# Digital_Isolation.net
KiCad netlist of a schematic drawn in Altium Designer
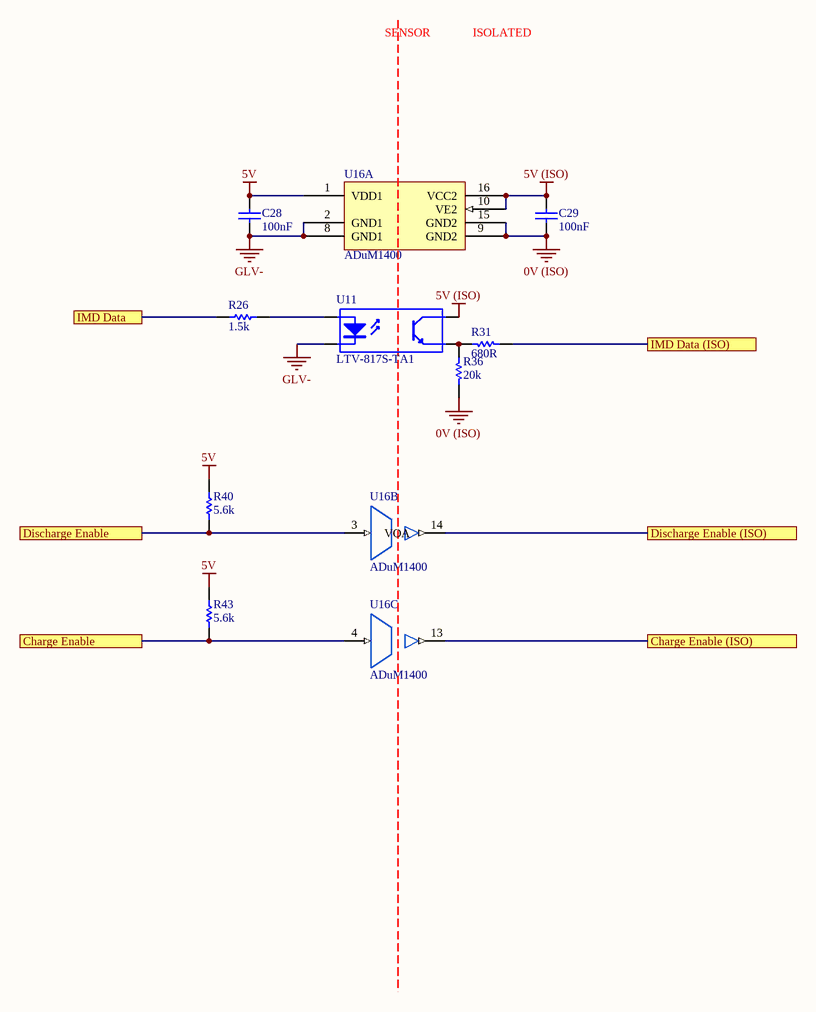
[diagram p0: Digital Isolation.SchDoc]

(export (version "E")
  (design (tool "Eeschema 10.0.6"))
  (components
    (comp (ref "C28")
      (value "100nF")
      (footprint "0805")
      (fields
        (field (name "PART NUMBER") "GCM21BR71E104KA37L")
        (field (name "TOLERANCE") "10%")
        (field (name "MANUFACTURER") "muRata")
      )
      (libsource (lib "ts_20-standard-library") (part "Capacitor"))
    )
    (comp (ref "C29")
      (value "100nF")
      (footprint "0805")
      (fields
        (field (name "PART NUMBER") "GCM21BR71E104KA37L")
        (field (name "TOLERANCE") "10%")
        (field (name "MANUFACTURER") "muRata")
      )
      (libsource (lib "ts_20-standard-library") (part "Capacitor"))
    )
    (comp (ref "R26")
      (value "1.5k")
      (footprint "0805")
      (fields
        (field (name "PART NUMBER") "RC0805FR071K5L")
        (field (name "MANUFACTURER") "YAGEO")
        (field (name "TOLERANCE") "0.01")
      )
      (libsource (lib "ts_20-standard-library") (part "Resistor"))
    )
    (comp (ref "R31")
      (value "680R")
      (footprint "0805")
      (fields
        (field (name "PART NUMBER") "RC0805FR07680RL")
        (field (name "MANUFACTURER") "YAGEO")
        (field (name "TOLERANCE") "0.01")
      )
      (libsource (lib "ts_20-standard-library") (part "Resistor"))
    )
    (comp (ref "R36")
      (value "20k")
      (footprint "0805")
      (fields
        (field (name "PART NUMBER") "RC0805FR0720KL")
        (field (name "MANUFACTURER") "YAGEO")
        (field (name "TOLERANCE") "0.01")
      )
      (libsource (lib "ts_20-standard-library") (part "Resistor"))
    )
    (comp (ref "R40")
      (value "5.6k")
      (footprint "0805")
      (fields
        (field (name "PART NUMBER") "RC0805FR075K6L")
        (field (name "MANUFACTURER") "YAGEO")
        (field (name "TOLERANCE") "0.01")
      )
      (libsource (lib "ts_20-standard-library") (part "Resistor"))
    )
    (comp (ref "R43")
      (value "5.6k")
      (footprint "0805")
      (fields
        (field (name "PART NUMBER") "RC0805FR075K6L")
        (field (name "MANUFACTURER") "YAGEO")
        (field (name "TOLERANCE") "0.01")
      )
      (libsource (lib "ts_20-standard-library") (part "Resistor"))
    )
    (comp (ref "U11")
      (value "LTV-817S-TA1")
      (footprint "ON 4-SMD")
      (description "35V 50ma Optocoupler (VF=1.2V)")
      (fields
        (field (name "MANUFACTURER") "Lite-On Inc")
        (field (name "DIGIKEY PART NUMBER") "160-1893-2-ND")
      )
      (libsource (lib "ts_20-standard-library") (part "LTV-817S-TA1"))
    )
    (comp (ref "U16")
      (value "ADuM1400")
      (footprint "AD 16-SOIC")
      (fields
        (field (name "MANUFACTURER") "Analog Devices")
        (field (name "DIGIKEY PART NUMBER") "ADUM1400WSRWZ-ND")
      )
      (libsource (lib "ts_20-standard-library") (part "ADuM1400"))
    )
  )
  (nets
    (net (code "1") (name "/Charge Enable") (class "Default")
      (node (ref "R43") (pin "1") (pinfunction "1_1") (pintype "passive"))
      (node (ref "U16") (pin "4") (pinfunction "VIB_4") (pintype "input"))
    )
    (net (code "2") (name "/Charge Enable (ISO)") (class "Default")
      (node (ref "U16") (pin "13") (pinfunction "VOB_13") (pintype "output"))
    )
    (net (code "3") (name "/Discharge Enable") (class "Default")
      (node (ref "R40") (pin "1") (pinfunction "1_1") (pintype "passive"))
      (node (ref "U16") (pin "3") (pinfunction "VIA_3") (pintype "input"))
    )
    (net (code "4") (name "/Discharge Enable (ISO)") (class "Default")
      (node (ref "U16") (pin "14") (pinfunction "VOA_14") (pintype "output"))
    )
    (net (code "5") (name "/IMD Data") (class "Default")
      (node (ref "R26") (pin "1") (pinfunction "1_1") (pintype "passive"))
    )
    (net (code "6") (name "/IMD Data (ISO)") (class "Default")
      (node (ref "R31") (pin "1") (pinfunction "1_1") (pintype "passive"))
    )
    (net (code "7") (name "0V (ISO)") (class "Default")
      (node (ref "C29") (pin "1") (pinfunction "1_1") (pintype "passive"))
      (node (ref "R36") (pin "1") (pinfunction "1_1") (pintype "passive"))
      (node (ref "U16") (pin "15") (pinfunction "GND2_15") (pintype "power_in"))
      (node (ref "U16") (pin "9") (pinfunction "GND2_9") (pintype "power_in"))
    )
    (net (code "8") (name "5V") (class "Default")
      (node (ref "C28") (pin "2") (pinfunction "2_2") (pintype "passive"))
      (node (ref "R40") (pin "2") (pinfunction "2_2") (pintype "passive"))
      (node (ref "R43") (pin "2") (pinfunction "2_2") (pintype "passive"))
      (node (ref "U16") (pin "1") (pinfunction "VDD1_1") (pintype "power_in"))
    )
    (net (code "9") (name "5V (ISO)") (class "Default")
      (node (ref "C29") (pin "2") (pinfunction "2_2") (pintype "passive"))
      (node (ref "U11") (pin "4") (pinfunction "C_4") (pintype "passive"))
      (node (ref "U16") (pin "10") (pinfunction "VE2_10") (pintype "input"))
      (node (ref "U16") (pin "16") (pinfunction "VCC2_16") (pintype "power_in"))
    )
    (net (code "10") (name "GLV-") (class "Default")
      (node (ref "C28") (pin "1") (pinfunction "1_1") (pintype "passive"))
      (node (ref "U11") (pin "2") (pinfunction "K_2") (pintype "passive"))
      (node (ref "U16") (pin "2") (pinfunction "GND1_2") (pintype "power_in"))
      (node (ref "U16") (pin "8") (pinfunction "GND1_8") (pintype "power_in"))
    )
    (net (code "11") (name "Net-(U11-A)") (class "Default")
      (node (ref "R26") (pin "2") (pinfunction "2_2") (pintype "passive"))
      (node (ref "U11") (pin "1") (pinfunction "A_1") (pintype "passive"))
    )
    (net (code "12") (name "Net-(U11-E)") (class "Default")
      (node (ref "R31") (pin "2") (pinfunction "2_2") (pintype "passive"))
      (node (ref "R36") (pin "2") (pinfunction "2_2") (pintype "passive"))
      (node (ref "U11") (pin "3") (pinfunction "E_3") (pintype "passive"))
    )
  )
)
